# pcb_all.net
KiCad netlist of a schematic drawn in EAGLE
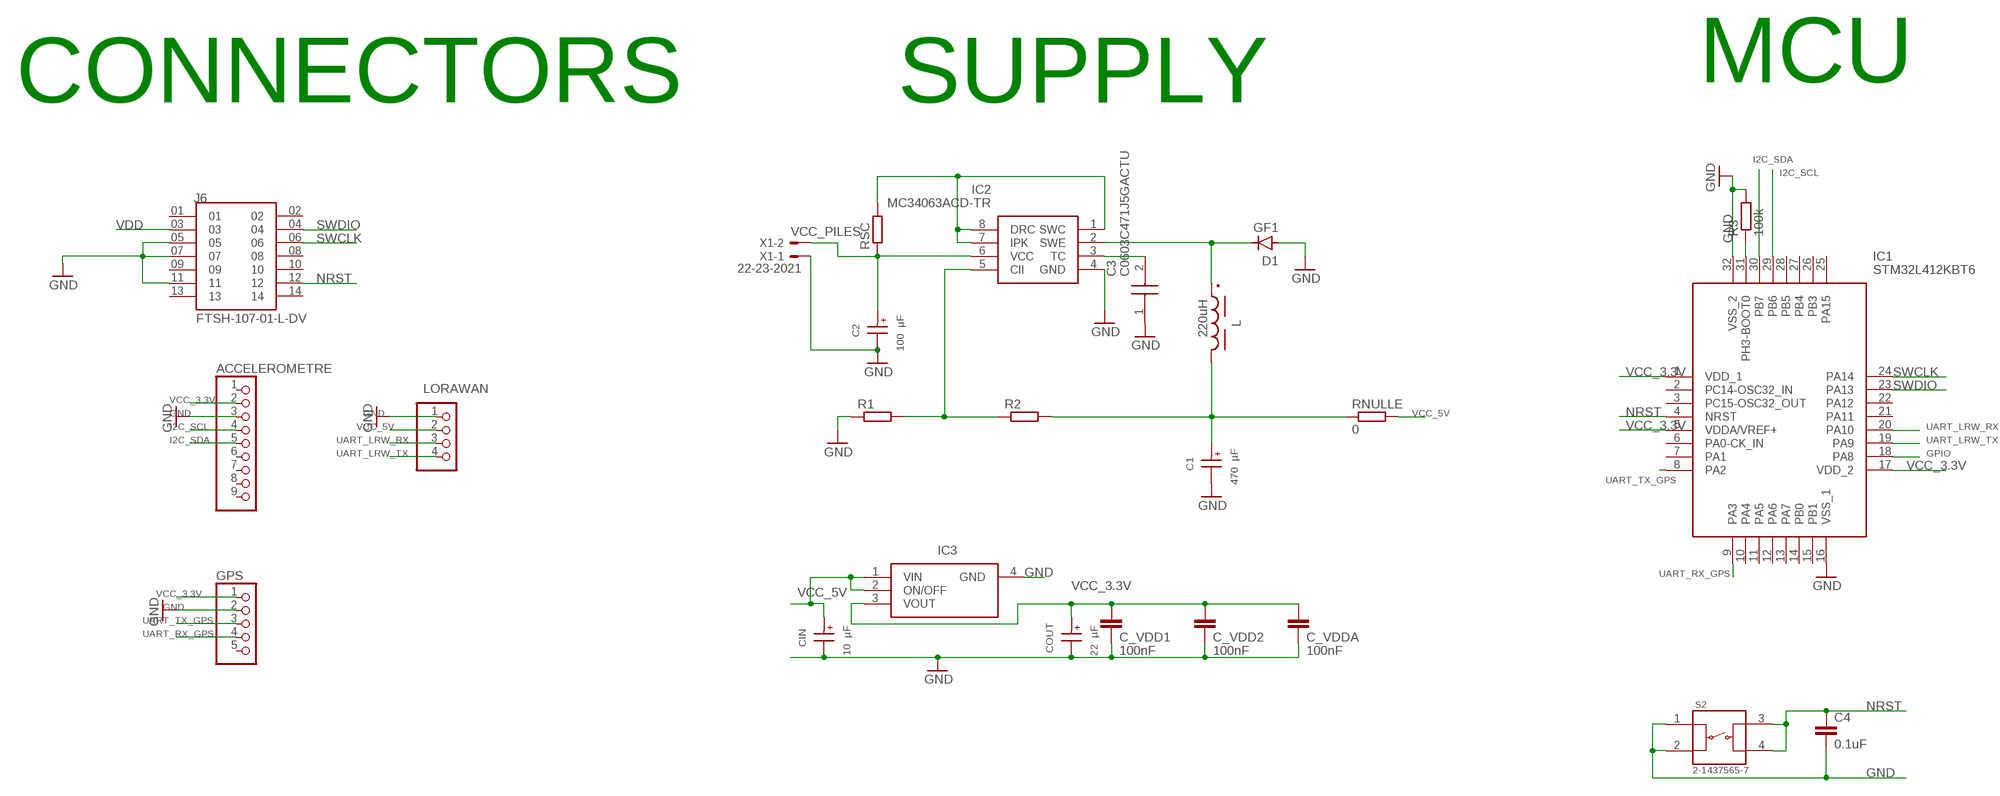
[diagram p0: schematic, sheet 1]

(export (version "E")
  (design (tool "Eeschema 10.0.6"))
  (components
    (comp (ref "ACCELEROMETRE")
      (value "PINHD-1X9")
      (footprint "eagle-import:1X09")
      (libsource (lib "eagle-import") (part "PINHD-1X9"))
    )
    (comp (ref "C1")
      (value "470 µF")
      (footprint "eagle-import:WCAP-ASLL_8X10.5(DXL)")
      (libsource (lib "eagle-import") (part "WCAP-ASLL_8X10.5_865060353009"))
    )
    (comp (ref "C2")
      (value "100 µF")
      (footprint "eagle-import:WCAP-ASLL_6.3X7.7(DXL)")
      (libsource (lib "eagle-import") (part "WCAP-ASLL_6.3X7.7_865060445005"))
    )
    (comp (ref "C3")
      (value "C0603C471J5GACTU")
      (footprint "eagle-import:C0603")
      (fields (field (name "MOUSER_PART_NUMBER") "80-C0603C471J5G"))
      (libsource (lib "eagle-import") (part "C0603C471J5GACTU"))
    )
    (comp (ref "C4")
      (value "0.1uF")
      (footprint "eagle-import:C0603")
      (libsource (lib "eagle-import") (part "C-EUC0603"))
    )
    (comp (ref "CIN")
      (value "10 µF")
      (footprint "eagle-import:WCAP-ASLL_4X5.5(DXL)")
      (libsource (lib "eagle-import") (part "WCAP-ASLL_4X5.5_865060440001"))
    )
    (comp (ref "COUT")
      (value "22 µF")
      (footprint "eagle-import:WCAP-ASLL_5X5.5(DXL)")
      (libsource (lib "eagle-import") (part "WCAP-ASLL_5X5.5_865060442002"))
    )
    (comp (ref "C_VDD1")
      (value "100nF")
      (footprint "eagle-import:C0603")
      (libsource (lib "eagle-import") (part "C-EUC0603"))
    )
    (comp (ref "C_VDD2")
      (value "100nF")
      (footprint "eagle-import:C0603")
      (libsource (lib "eagle-import") (part "C-EUC0603"))
    )
    (comp (ref "C_VDDA")
      (value "100nF")
      (footprint "eagle-import:C0603")
      (libsource (lib "eagle-import") (part "C-EUC0603"))
    )
    (comp (ref "D1")
      (value "GF1")
      (footprint "eagle-import:SMA-DO214AC")
      (libsource (lib "eagle-import") (part "GF1"))
    )
    (comp (ref "GPS")
      (value "PINHD-1X5")
      (footprint "eagle-import:1X05")
      (libsource (lib "eagle-import") (part "PINHD-1X5"))
    )
    (comp (ref "IC1")
      (value "STM32L412KBT6")
      (footprint "eagle-import:QFP80P900X900X160-32N")
      (fields (field (name "MOUSER_PART_NUMBER") "511-STM32L412KBT6"))
      (libsource (lib "eagle-import") (part "STM32L412KBT6"))
    )
    (comp (ref "IC2")
      (value "MC34063ACD-TR")
      (footprint "eagle-import:SOIC127P600X175-8N")
      (fields (field (name "MOUSER_PART_NUMBER") "511-MC34063ACD-TR"))
      (libsource (lib "eagle-import") (part "MC34063ACD-TR"))
    )
    (comp (ref "IC3")
      (value "NCV33375ST3.3T3G")
      (footprint "eagle-import:SOT230P700X175-4N")
      (fields (field (name "MOUSER_PART_NUMBER") "863-NCV33375ST3.3T3G"))
      (libsource (lib "eagle-import") (part "NCV33375ST3.3T3G"))
    )
    (comp (ref "J6")
      (value "FTSH-107-01-L-DV")
      (footprint "eagle-import:SAMTEC_FTSH-107-01-L-DV")
      (fields (field (name "MANUFACTURER") "Samtec"))
      (libsource (lib "eagle-import") (part "FTSH-107-01-L-DV"))
    )
    (comp (ref "L")
      (value "220uH")
      (footprint "eagle-import:WE-PDA_1260")
      (libsource (lib "eagle-import") (part "WE-PDA_1260_784771221"))
    )
    (comp (ref "LORAWAN")
      (value "PINHD-1X4")
      (footprint "eagle-import:1X04")
      (libsource (lib "eagle-import") (part "PINHD-1X4"))
    )
    (comp (ref "R1")
      (value "R-EU_R0603")
      (footprint "eagle-import:R0603")
      (libsource (lib "eagle-import") (part "R-EU_R0603"))
    )
    (comp (ref "R2")
      (value "R-EU_R0603")
      (footprint "eagle-import:R0603")
      (libsource (lib "eagle-import") (part "R-EU_R0603"))
    )
    (comp (ref "R3")
      (value "100k")
      (footprint "eagle-import:R0603")
      (libsource (lib "eagle-import") (part "R-EU_R0603"))
    )
    (comp (ref "RNULLE")
      (value "0")
      (footprint "eagle-import:R0603")
      (libsource (lib "eagle-import") (part "R-EU_R0603"))
    )
    (comp (ref "RSC")
      (value "R-EU_R1206W")
      (footprint "eagle-import:R1206W")
      (libsource (lib "eagle-import") (part "R-EU_R1206W"))
    )
    (comp (ref "S2")
      (value "2-1437565-7")
      (footprint "eagle-import:SW_2-1437565-7")
      (fields (field (name "MF") "TE Connectivity") (field (name "MP") "FSM2JSMA"))
      (libsource (lib "eagle-import") (part "2-1437565-7"))
    )
    (comp (ref "X1")
      (value "22-23-2021")
      (footprint "eagle-import:22-23-2021")
      (fields (field (name "MF") "MOLEX"))
      (libsource (lib "eagle-import") (part "22-23-2021"))
    )
  )
  (nets
    (net (code "1") (name "/GPIO") (class "Default")
      (node (ref "IC1") (pin "18") (pinfunction "PA8_18") (pintype "bidirectional"))
    )
    (net (code "2") (name "/I2C_SCL") (class "Default")
      (node (ref "ACCELEROMETRE") (pin "4") (pinfunction "4_4") (pintype "passive"))
      (node (ref "IC1") (pin "29") (pinfunction "PB6_29") (pintype "bidirectional"))
    )
    (net (code "3") (name "/I2C_SDA") (class "Default")
      (node (ref "ACCELEROMETRE") (pin "5") (pinfunction "5_5") (pintype "passive"))
      (node (ref "IC1") (pin "30") (pinfunction "PB7_30") (pintype "bidirectional"))
    )
    (net (code "4") (name "/NRST") (class "Default")
      (node (ref "C4") (pin "1") (pinfunction "1_1") (pintype "passive"))
      (node (ref "IC1") (pin "4") (pinfunction "NRST_4") (pintype "input"))
      (node (ref "J6") (pin "12") (pinfunction "12_12") (pintype "passive"))
      (node (ref "S2") (pin "3") (pinfunction "3_3") (pintype "passive"))
      (node (ref "S2") (pin "4") (pinfunction "4_4") (pintype "passive"))
    )
    (net (code "5") (name "/SWCLK") (class "Default")
      (node (ref "IC1") (pin "24") (pinfunction "PA14_24") (pintype "bidirectional"))
      (node (ref "J6") (pin "06") (pinfunction "06_06") (pintype "passive"))
    )
    (net (code "6") (name "/SWDIO") (class "Default")
      (node (ref "IC1") (pin "23") (pinfunction "PA13_23") (pintype "bidirectional"))
      (node (ref "J6") (pin "04") (pinfunction "04_04") (pintype "passive"))
    )
    (net (code "7") (name "/UART_LRW_RX") (class "Default")
      (node (ref "IC1") (pin "20") (pinfunction "PA10_20") (pintype "bidirectional"))
      (node (ref "LORAWAN") (pin "3") (pinfunction "3_3") (pintype "passive"))
    )
    (net (code "8") (name "/UART_LRW_TX") (class "Default")
      (node (ref "IC1") (pin "19") (pinfunction "PA9_19") (pintype "bidirectional"))
      (node (ref "LORAWAN") (pin "4") (pinfunction "4_4") (pintype "passive"))
    )
    (net (code "9") (name "/UART_RX_GPS") (class "Default")
      (node (ref "GPS") (pin "4") (pinfunction "4_4") (pintype "passive"))
      (node (ref "IC1") (pin "9") (pinfunction "PA3_9") (pintype "bidirectional"))
    )
    (net (code "10") (name "/UART_TX_GPS") (class "Default")
      (node (ref "GPS") (pin "3") (pinfunction "3_3") (pintype "passive"))
      (node (ref "IC1") (pin "8") (pinfunction "PA2_8") (pintype "bidirectional"))
    )
    (net (code "11") (name "/VCC_3.3V") (class "Default")
      (node (ref "ACCELEROMETRE") (pin "2") (pinfunction "2_2") (pintype "passive"))
      (node (ref "COUT") (pin "1") (pinfunction "+_1") (pintype "passive"))
      (node (ref "C_VDD1") (pin "1") (pinfunction "1_1") (pintype "passive"))
      (node (ref "C_VDD2") (pin "1") (pinfunction "1_1") (pintype "passive"))
      (node (ref "C_VDDA") (pin "1") (pinfunction "1_1") (pintype "passive"))
      (node (ref "GPS") (pin "1") (pinfunction "1_1") (pintype "passive"))
      (node (ref "IC1") (pin "1") (pinfunction "VDD_1_1") (pintype "power_in"))
      (node (ref "IC1") (pin "17") (pinfunction "VDD_2_17") (pintype "power_in"))
      (node (ref "IC1") (pin "5") (pinfunction "VDDA/VREF+_5") (pintype "power_in"))
      (node (ref "IC3") (pin "3") (pinfunction "VOUT_3") (pintype "bidirectional"))
    )
    (net (code "12") (name "/VCC_5V") (class "Default")
      (node (ref "CIN") (pin "1") (pinfunction "+_1") (pintype "passive"))
      (node (ref "IC3") (pin "1") (pinfunction "VIN_1") (pintype "bidirectional"))
      (node (ref "IC3") (pin "2") (pinfunction "ON/OFF_2") (pintype "bidirectional"))
      (node (ref "LORAWAN") (pin "2") (pinfunction "2_2") (pintype "passive"))
      (node (ref "RNULLE") (pin "2") (pinfunction "2_2") (pintype "passive"))
    )
    (net (code "13") (name "/VCC_PILES") (class "Default")
      (node (ref "C2") (pin "1") (pinfunction "+_1") (pintype "passive"))
      (node (ref "IC2") (pin "6") (pinfunction "VCC_6") (pintype "bidirectional"))
      (node (ref "RSC") (pin "1") (pinfunction "1_1") (pintype "passive"))
      (node (ref "X1") (pin "2") (pinfunction "S_2") (pintype "passive"))
    )
    (net (code "14") (name "/VDD") (class "Default")
      (node (ref "J6") (pin "03") (pinfunction "03_03") (pintype "passive"))
    )
    (net (code "15") (name "GND") (class "Default")
      (node (ref "ACCELEROMETRE") (pin "3") (pinfunction "3_3") (pintype "passive"))
      (node (ref "C1") (pin "2") (pinfunction "-_2") (pintype "passive"))
      (node (ref "C2") (pin "2") (pinfunction "-_2") (pintype "passive"))
      (node (ref "C3") (pin "1") (pinfunction "1_1") (pintype "bidirectional"))
      (node (ref "C4") (pin "2") (pinfunction "2_2") (pintype "passive"))
      (node (ref "CIN") (pin "2") (pinfunction "-_2") (pintype "passive"))
      (node (ref "COUT") (pin "2") (pinfunction "-_2") (pintype "passive"))
      (node (ref "C_VDD1") (pin "2") (pinfunction "2_2") (pintype "passive"))
      (node (ref "C_VDD2") (pin "2") (pinfunction "2_2") (pintype "passive"))
      (node (ref "C_VDDA") (pin "2") (pinfunction "2_2") (pintype "passive"))
      (node (ref "D1") (pin "A") (pinfunction "A_A") (pintype "passive"))
      (node (ref "GPS") (pin "2") (pinfunction "2_2") (pintype "passive"))
      (node (ref "IC1") (pin "16") (pinfunction "VSS_1_16") (pintype "power_in"))
      (node (ref "IC1") (pin "32") (pinfunction "VSS_2_32") (pintype "power_in"))
      (node (ref "IC2") (pin "4") (pinfunction "GND_4") (pintype "bidirectional"))
      (node (ref "IC3") (pin "4") (pinfunction "GND_4") (pintype "bidirectional"))
      (node (ref "J6") (pin "05") (pinfunction "05_05") (pintype "passive"))
      (node (ref "J6") (pin "07") (pinfunction "07_07") (pintype "passive"))
      (node (ref "J6") (pin "11") (pinfunction "11_11") (pintype "passive"))
      (node (ref "LORAWAN") (pin "1") (pinfunction "1_1") (pintype "passive"))
      (node (ref "R1") (pin "1") (pinfunction "1_1") (pintype "passive"))
      (node (ref "R3") (pin "2") (pinfunction "2_2") (pintype "passive"))
      (node (ref "S2") (pin "1") (pinfunction "1_1") (pintype "passive"))
      (node (ref "S2") (pin "2") (pinfunction "2_2") (pintype "passive"))
      (node (ref "X1") (pin "1") (pinfunction "S_1") (pintype "passive"))
    )
    (net (code "16") (name "Net-(C1-+)") (class "Default")
      (node (ref "C1") (pin "1") (pinfunction "+_1") (pintype "passive"))
      (node (ref "L") (pin "2") (pinfunction "2_2") (pintype "passive"))
      (node (ref "R2") (pin "2") (pinfunction "2_2") (pintype "passive"))
      (node (ref "RNULLE") (pin "1") (pinfunction "1_1") (pintype "passive"))
    )
    (net (code "17") (name "Net-(D1-C)") (class "Default")
      (node (ref "D1") (pin "K") (pinfunction "C_K") (pintype "passive"))
      (node (ref "IC2") (pin "2") (pinfunction "SWE_2") (pintype "bidirectional"))
      (node (ref "L") (pin "1") (pinfunction "1_1") (pintype "passive"))
    )
    (net (code "18") (name "Net-(IC1-PH3-BOOT0)") (class "Default")
      (node (ref "IC1") (pin "31") (pinfunction "PH3-BOOT0_31") (pintype "bidirectional"))
      (node (ref "R3") (pin "1") (pinfunction "1_1") (pintype "passive"))
    )
    (net (code "19") (name "Net-(IC2-CII)") (class "Default")
      (node (ref "IC2") (pin "5") (pinfunction "CII_5") (pintype "bidirectional"))
      (node (ref "R1") (pin "2") (pinfunction "2_2") (pintype "passive"))
      (node (ref "R2") (pin "1") (pinfunction "1_1") (pintype "passive"))
    )
    (net (code "20") (name "Net-(IC2-DRC)") (class "Default")
      (node (ref "IC2") (pin "1") (pinfunction "SWC_1") (pintype "bidirectional"))
      (node (ref "IC2") (pin "7") (pinfunction "IPK_7") (pintype "bidirectional"))
      (node (ref "IC2") (pin "8") (pinfunction "DRC_8") (pintype "bidirectional"))
      (node (ref "RSC") (pin "2") (pinfunction "2_2") (pintype "passive"))
    )
    (net (code "21") (name "Net-(IC2-TC)") (class "Default")
      (node (ref "C3") (pin "2") (pinfunction "2_2") (pintype "bidirectional"))
      (node (ref "IC2") (pin "3") (pinfunction "TC_3") (pintype "bidirectional"))
    )
    (net (code "22") (name "unconnected-(ACCELEROMETRE-Pad1)") (class "Default")
      (node (ref "ACCELEROMETRE") (pin "1") (pinfunction "1_1") (pintype "passive"))
    )
    (net (code "23") (name "unconnected-(ACCELEROMETRE-Pad6)") (class "Default")
      (node (ref "ACCELEROMETRE") (pin "6") (pinfunction "6_6") (pintype "passive"))
    )
    (net (code "24") (name "unconnected-(ACCELEROMETRE-Pad7)") (class "Default")
      (node (ref "ACCELEROMETRE") (pin "7") (pinfunction "7_7") (pintype "passive"))
    )
    (net (code "25") (name "unconnected-(ACCELEROMETRE-Pad8)") (class "Default")
      (node (ref "ACCELEROMETRE") (pin "8") (pinfunction "8_8") (pintype "passive"))
    )
    (net (code "26") (name "unconnected-(ACCELEROMETRE-Pad9)") (class "Default")
      (node (ref "ACCELEROMETRE") (pin "9") (pinfunction "9_9") (pintype "passive"))
    )
    (net (code "27") (name "unconnected-(GPS-Pad5)") (class "Default")
      (node (ref "GPS") (pin "5") (pinfunction "5_5") (pintype "passive"))
    )
    (net (code "28") (name "unconnected-(IC1-PA0-CK_IN-Pad6)") (class "Default")
      (node (ref "IC1") (pin "6") (pinfunction "PA0-CK_IN_6") (pintype "bidirectional"))
    )
    (net (code "29") (name "unconnected-(IC1-PA1-Pad7)") (class "Default")
      (node (ref "IC1") (pin "7") (pinfunction "PA1_7") (pintype "bidirectional"))
    )
    (net (code "30") (name "unconnected-(IC1-PA4-Pad10)") (class "Default")
      (node (ref "IC1") (pin "10") (pinfunction "PA4_10") (pintype "bidirectional"))
    )
    (net (code "31") (name "unconnected-(IC1-PA5-Pad11)") (class "Default")
      (node (ref "IC1") (pin "11") (pinfunction "PA5_11") (pintype "bidirectional"))
    )
    (net (code "32") (name "unconnected-(IC1-PA6-Pad12)") (class "Default")
      (node (ref "IC1") (pin "12") (pinfunction "PA6_12") (pintype "bidirectional"))
    )
    (net (code "33") (name "unconnected-(IC1-PA7-Pad13)") (class "Default")
      (node (ref "IC1") (pin "13") (pinfunction "PA7_13") (pintype "bidirectional"))
    )
    (net (code "34") (name "unconnected-(IC1-PA11-Pad21)") (class "Default")
      (node (ref "IC1") (pin "21") (pinfunction "PA11_21") (pintype "bidirectional"))
    )
    (net (code "35") (name "unconnected-(IC1-PA12-Pad22)") (class "Default")
      (node (ref "IC1") (pin "22") (pinfunction "PA12_22") (pintype "bidirectional"))
    )
    (net (code "36") (name "unconnected-(IC1-PA15-Pad25)") (class "Default")
      (node (ref "IC1") (pin "25") (pinfunction "PA15_25") (pintype "bidirectional"))
    )
    (net (code "37") (name "unconnected-(IC1-PB0-Pad14)") (class "Default")
      (node (ref "IC1") (pin "14") (pinfunction "PB0_14") (pintype "bidirectional"))
    )
    (net (code "38") (name "unconnected-(IC1-PB1-Pad15)") (class "Default")
      (node (ref "IC1") (pin "15") (pinfunction "PB1_15") (pintype "bidirectional"))
    )
    (net (code "39") (name "unconnected-(IC1-PB3-Pad26)") (class "Default")
      (node (ref "IC1") (pin "26") (pinfunction "PB3_26") (pintype "bidirectional"))
    )
    (net (code "40") (name "unconnected-(IC1-PB4-Pad27)") (class "Default")
      (node (ref "IC1") (pin "27") (pinfunction "PB4_27") (pintype "bidirectional"))
    )
    (net (code "41") (name "unconnected-(IC1-PB5-Pad28)") (class "Default")
      (node (ref "IC1") (pin "28") (pinfunction "PB5_28") (pintype "bidirectional"))
    )
    (net (code "42") (name "unconnected-(IC1-PC14-OSC32_IN-Pad2)") (class "Default")
      (node (ref "IC1") (pin "2") (pinfunction "PC14-OSC32_IN_2") (pintype "bidirectional"))
    )
    (net (code "43") (name "unconnected-(IC1-PC15-OSC32_OUT-Pad3)") (class "Default")
      (node (ref "IC1") (pin "3") (pinfunction "PC15-OSC32_OUT_3") (pintype "bidirectional"))
    )
    (net (code "44") (name "unconnected-(J6-Pad01)") (class "Default")
      (node (ref "J6") (pin "01") (pinfunction "01_01") (pintype "passive"))
    )
    (net (code "45") (name "unconnected-(J6-Pad02)") (class "Default")
      (node (ref "J6") (pin "02") (pinfunction "02_02") (pintype "passive"))
    )
    (net (code "46") (name "unconnected-(J6-Pad08)") (class "Default")
      (node (ref "J6") (pin "08") (pinfunction "08_08") (pintype "passive"))
    )
    (net (code "47") (name "unconnected-(J6-Pad09)") (class "Default")
      (node (ref "J6") (pin "09") (pinfunction "09_09") (pintype "passive"))
    )
    (net (code "48") (name "unconnected-(J6-Pad10)") (class "Default")
      (node (ref "J6") (pin "10") (pinfunction "10_10") (pintype "passive"))
    )
    (net (code "49") (name "unconnected-(J6-Pad13)") (class "Default")
      (node (ref "J6") (pin "13") (pinfunction "13_13") (pintype "passive"))
    )
    (net (code "50") (name "unconnected-(J6-Pad14)") (class "Default")
      (node (ref "J6") (pin "14") (pinfunction "14_14") (pintype "passive"))
    )
  )
)
